# Versa64Cart_v1_3.net
KiCad netlist of a schematic drawn in EAGLE
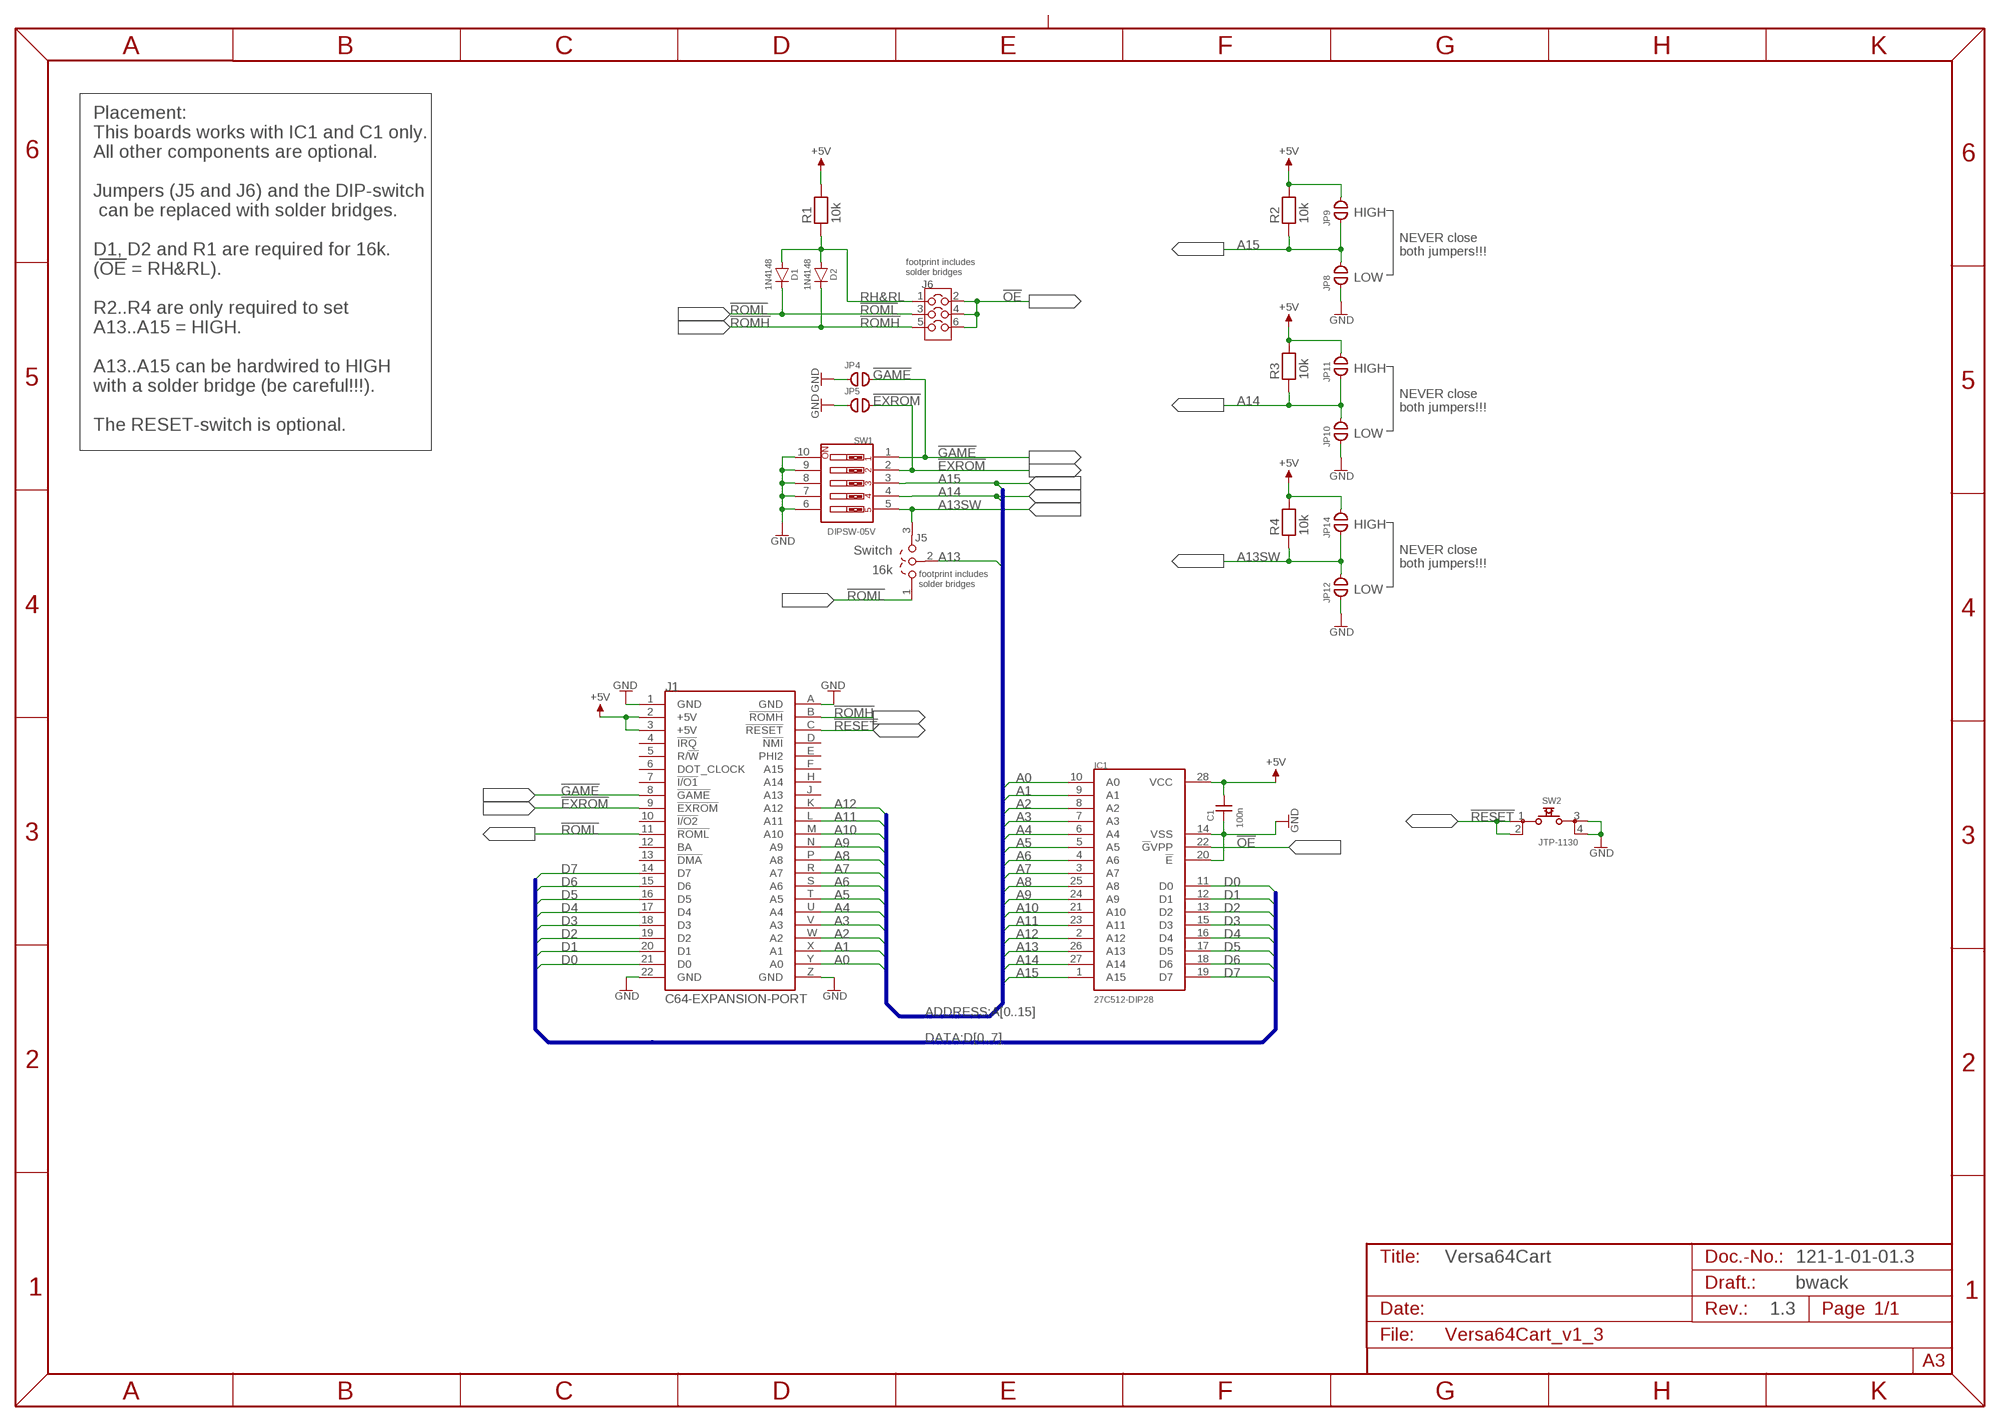
[diagram p0: schematic, sheet 1]

(export (version "E")
  (design (tool "Eeschema 10.0.6"))
  (components
    (comp (ref "C1")
      (value "100n")
      (footprint "eagle-import:C-2,5")
      (libsource (lib "eagle-import") (part "CAP01"))
    )
    (comp (ref "D1")
      (value "1N4148")
      (footprint "eagle-import:DO-35")
      (libsource (lib "eagle-import") (part "1N4148"))
    )
    (comp (ref "D2")
      (value "1N4148")
      (footprint "eagle-import:DO-35")
      (libsource (lib "eagle-import") (part "1N4148"))
    )
    (comp (ref "IC1")
      (value "27C512-DIP28")
      (footprint "eagle-import:DIL28-6")
      (libsource (lib "eagle-import") (part "M27C512-DIP28"))
    )
    (comp (ref "J1")
      (value "C64-EXPANSION-PORT")
      (footprint "eagle-import:EXPPORT")
      (libsource (lib "eagle-import") (part "C64-EXPANSIONP"))
    )
    (comp (ref "J5")
      (value "COMBI-3P")
      (footprint "eagle-import:COMBI-3P")
      (libsource (lib "eagle-import") (part "COMBI-3P"))
    )
    (comp (ref "J6")
      (value "COMBI-3X2P")
      (footprint "eagle-import:COMBI-3X2")
      (fields (field (name "SPICEPREFIX") "X"))
      (libsource (lib "eagle-import") (part "COMBI-3X2P"))
    )
    (comp (ref "JP4")
      (value "OPEN")
      (footprint "eagle-import:CP_OP")
      (libsource (lib "eagle-import") (part "OPEN"))
    )
    (comp (ref "JP5")
      (value "OPEN")
      (footprint "eagle-import:CP_OP")
      (libsource (lib "eagle-import") (part "OPEN"))
    )
    (comp (ref "JP8")
      (value "OPEN")
      (footprint "eagle-import:CP_OP")
      (libsource (lib "eagle-import") (part "OPEN"))
    )
    (comp (ref "JP9")
      (value "OPEN")
      (footprint "eagle-import:CP_OP")
      (libsource (lib "eagle-import") (part "OPEN"))
    )
    (comp (ref "JP10")
      (value "OPEN")
      (footprint "eagle-import:CP_OP")
      (libsource (lib "eagle-import") (part "OPEN"))
    )
    (comp (ref "JP11")
      (value "OPEN")
      (footprint "eagle-import:CP_OP")
      (libsource (lib "eagle-import") (part "OPEN"))
    )
    (comp (ref "JP12")
      (value "OPEN")
      (footprint "eagle-import:CP_OP")
      (libsource (lib "eagle-import") (part "OPEN"))
    )
    (comp (ref "JP14")
      (value "OPEN")
      (footprint "eagle-import:CP_OP")
      (libsource (lib "eagle-import") (part "OPEN"))
    )
    (comp (ref "R1")
      (value "10k")
      (footprint "eagle-import:R-10")
      (libsource (lib "eagle-import") (part "RES04"))
    )
    (comp (ref "R2")
      (value "10k")
      (footprint "eagle-import:R-10")
      (libsource (lib "eagle-import") (part "RES04"))
    )
    (comp (ref "R3")
      (value "10k")
      (footprint "eagle-import:R-10")
      (libsource (lib "eagle-import") (part "RES04"))
    )
    (comp (ref "R4")
      (value "10k")
      (footprint "eagle-import:R-10")
      (libsource (lib "eagle-import") (part "RES04"))
    )
    (comp (ref "SW1")
      (value "DIPSW-05V")
      (footprint "eagle-import:DIPSW-05V")
      (libsource (lib "eagle-import") (part "DIPSW-05V"))
    )
    (comp (ref "SW2")
      (value "JTP-1130")
      (footprint "eagle-import:JTP-1130")
      (libsource (lib "eagle-import") (part "JTP-1130"))
    )
  )
  (nets
    (net (code "25") (name "+5V") (class "Default")
      (node (ref "C1") (pin "2") (pinfunction "2_2") (pintype "passive"))
      (node (ref "IC1") (pin "28") (pinfunction "VCC_28") (pintype "power_in"))
      (node (ref "J1") (pin "2") (pinfunction "+5V_2") (pintype "power_in"))
      (node (ref "J1") (pin "3") (pinfunction "+5V_3") (pintype "power_in"))
      (node (ref "JP11") (pin "2") (pinfunction "2_2") (pintype "passive"))
      (node (ref "JP14") (pin "2") (pinfunction "2_2") (pintype "passive"))
      (node (ref "JP9") (pin "2") (pinfunction "2_2") (pintype "passive"))
      (node (ref "R1") (pin "2") (pinfunction "2_2") (pintype "passive"))
      (node (ref "R2") (pin "2") (pinfunction "2_2") (pintype "passive"))
      (node (ref "R3") (pin "2") (pinfunction "2_2") (pintype "passive"))
      (node (ref "R4") (pin "2") (pinfunction "2_2") (pintype "passive"))
    )
    (net (code "26") (name "/A0") (class "Default")
      (node (ref "IC1") (pin "10") (pinfunction "A0_10") (pintype "input"))
      (node (ref "J1") (pin "Y") (pinfunction "A0_Y") (pintype "bidirectional"))
    )
    (net (code "27") (name "/A1") (class "Default")
      (node (ref "IC1") (pin "9") (pinfunction "A1_9") (pintype "input"))
      (node (ref "J1") (pin "X") (pinfunction "A1_X") (pintype "bidirectional"))
    )
    (net (code "28") (name "/A2") (class "Default")
      (node (ref "IC1") (pin "8") (pinfunction "A2_8") (pintype "input"))
      (node (ref "J1") (pin "W") (pinfunction "A2_W") (pintype "bidirectional"))
    )
    (net (code "29") (name "/A3") (class "Default")
      (node (ref "IC1") (pin "7") (pinfunction "A3_7") (pintype "input"))
      (node (ref "J1") (pin "V") (pinfunction "A3_V") (pintype "bidirectional"))
    )
    (net (code "30") (name "/A4") (class "Default")
      (node (ref "IC1") (pin "6") (pinfunction "A4_6") (pintype "input"))
      (node (ref "J1") (pin "U") (pinfunction "A4_U") (pintype "bidirectional"))
    )
    (net (code "31") (name "/A5") (class "Default")
      (node (ref "IC1") (pin "5") (pinfunction "A5_5") (pintype "input"))
      (node (ref "J1") (pin "T") (pinfunction "A5_T") (pintype "bidirectional"))
    )
    (net (code "32") (name "/A6") (class "Default")
      (node (ref "IC1") (pin "4") (pinfunction "A6_4") (pintype "input"))
      (node (ref "J1") (pin "S") (pinfunction "A6_S") (pintype "bidirectional"))
    )
    (net (code "33") (name "/A7") (class "Default")
      (node (ref "IC1") (pin "3") (pinfunction "A7_3") (pintype "input"))
      (node (ref "J1") (pin "R") (pinfunction "A7_R") (pintype "bidirectional"))
    )
    (net (code "34") (name "/A8") (class "Default")
      (node (ref "IC1") (pin "25") (pinfunction "A8_25") (pintype "input"))
      (node (ref "J1") (pin "P") (pinfunction "A8_P") (pintype "bidirectional"))
    )
    (net (code "35") (name "/A9") (class "Default")
      (node (ref "IC1") (pin "24") (pinfunction "A9_24") (pintype "input"))
      (node (ref "J1") (pin "N") (pinfunction "A9_N") (pintype "bidirectional"))
    )
    (net (code "36") (name "/A10") (class "Default")
      (node (ref "IC1") (pin "21") (pinfunction "A10_21") (pintype "input"))
      (node (ref "J1") (pin "M") (pinfunction "A10_M") (pintype "bidirectional"))
    )
    (net (code "37") (name "/A11") (class "Default")
      (node (ref "IC1") (pin "23") (pinfunction "A11_23") (pintype "input"))
      (node (ref "J1") (pin "L") (pinfunction "A11_L") (pintype "bidirectional"))
    )
    (net (code "38") (name "/A12") (class "Default")
      (node (ref "IC1") (pin "2") (pinfunction "A12_2") (pintype "input"))
      (node (ref "J1") (pin "K") (pinfunction "A12_K") (pintype "bidirectional"))
    )
    (net (code "39") (name "/A13") (class "Default")
      (node (ref "IC1") (pin "26") (pinfunction "A13_26") (pintype "input"))
      (node (ref "J5") (pin "2") (pinfunction "2_2") (pintype "bidirectional"))
    )
    (net (code "40") (name "/A13SW") (class "Default")
      (node (ref "J5") (pin "3") (pinfunction "3_3") (pintype "bidirectional"))
      (node (ref "JP12") (pin "2") (pinfunction "2_2") (pintype "passive"))
      (node (ref "JP14") (pin "1") (pinfunction "1_1") (pintype "passive"))
      (node (ref "R4") (pin "1") (pinfunction "1_1") (pintype "passive"))
      (node (ref "SW1") (pin "5") (pinfunction "5_5") (pintype "passive"))
    )
    (net (code "41") (name "/A14") (class "Default")
      (node (ref "IC1") (pin "27") (pinfunction "A14_27") (pintype "input"))
      (node (ref "JP10") (pin "2") (pinfunction "2_2") (pintype "passive"))
      (node (ref "JP11") (pin "1") (pinfunction "1_1") (pintype "passive"))
      (node (ref "R3") (pin "1") (pinfunction "1_1") (pintype "passive"))
      (node (ref "SW1") (pin "4") (pinfunction "4_4") (pintype "passive"))
    )
    (net (code "42") (name "/A15") (class "Default")
      (node (ref "IC1") (pin "1") (pinfunction "A15_1") (pintype "input"))
      (node (ref "JP8") (pin "2") (pinfunction "2_2") (pintype "passive"))
      (node (ref "JP9") (pin "1") (pinfunction "1_1") (pintype "passive"))
      (node (ref "R2") (pin "1") (pinfunction "1_1") (pintype "passive"))
      (node (ref "SW1") (pin "3") (pinfunction "3_3") (pintype "passive"))
    )
    (net (code "44") (name "/D0") (class "Default")
      (node (ref "IC1") (pin "11") (pinfunction "D0_11") (pintype "bidirectional"))
      (node (ref "J1") (pin "21") (pinfunction "D0_21") (pintype "bidirectional"))
    )
    (net (code "45") (name "/D1") (class "Default")
      (node (ref "IC1") (pin "12") (pinfunction "D1_12") (pintype "bidirectional"))
      (node (ref "J1") (pin "20") (pinfunction "D1_20") (pintype "bidirectional"))
    )
    (net (code "46") (name "/D2") (class "Default")
      (node (ref "IC1") (pin "13") (pinfunction "D2_13") (pintype "bidirectional"))
      (node (ref "J1") (pin "19") (pinfunction "D2_19") (pintype "bidirectional"))
    )
    (net (code "47") (name "/D3") (class "Default")
      (node (ref "IC1") (pin "15") (pinfunction "D3_15") (pintype "bidirectional"))
      (node (ref "J1") (pin "18") (pinfunction "D3_18") (pintype "bidirectional"))
    )
    (net (code "48") (name "/D4") (class "Default")
      (node (ref "IC1") (pin "16") (pinfunction "D4_16") (pintype "bidirectional"))
      (node (ref "J1") (pin "17") (pinfunction "D4_17") (pintype "bidirectional"))
    )
    (net (code "49") (name "/D5") (class "Default")
      (node (ref "IC1") (pin "17") (pinfunction "D5_17") (pintype "bidirectional"))
      (node (ref "J1") (pin "16") (pinfunction "D5_16") (pintype "bidirectional"))
    )
    (net (code "50") (name "/D6") (class "Default")
      (node (ref "IC1") (pin "18") (pinfunction "D6_18") (pintype "bidirectional"))
      (node (ref "J1") (pin "15") (pinfunction "D6_15") (pintype "bidirectional"))
    )
    (net (code "51") (name "/D7") (class "Default")
      (node (ref "IC1") (pin "19") (pinfunction "D7_19") (pintype "bidirectional"))
      (node (ref "J1") (pin "14") (pinfunction "D7_14") (pintype "bidirectional"))
    )
    (net (code "53") (name "/RH&RL") (class "Default")
      (node (ref "D1") (pin "A") (pinfunction "A_A") (pintype "passive"))
      (node (ref "D2") (pin "A") (pinfunction "A_A") (pintype "passive"))
      (node (ref "J6") (pin "1") (pinfunction "1_1") (pintype "bidirectional"))
      (node (ref "R1") (pin "1") (pinfunction "1_1") (pintype "passive"))
    )
    (net (code "54") (name "/~{EXROM}") (class "Default")
      (node (ref "J1") (pin "9") (pinfunction "~{EXROM}_9") (pintype "input"))
      (node (ref "JP5") (pin "2") (pinfunction "2_2") (pintype "passive"))
      (node (ref "SW1") (pin "2") (pinfunction "2_2") (pintype "passive"))
    )
    (net (code "55") (name "/~{GAME}") (class "Default")
      (node (ref "J1") (pin "8") (pinfunction "~{GAME}_8") (pintype "input"))
      (node (ref "JP4") (pin "2") (pinfunction "2_2") (pintype "passive"))
      (node (ref "SW1") (pin "1") (pinfunction "1_1") (pintype "passive"))
    )
    (net (code "56") (name "/~{OE}") (class "Default")
      (node (ref "IC1") (pin "22") (pinfunction "~{G}VPP_22") (pintype "input"))
      (node (ref "J6") (pin "2") (pinfunction "2_2") (pintype "bidirectional"))
      (node (ref "J6") (pin "4") (pinfunction "4_4") (pintype "bidirectional"))
      (node (ref "J6") (pin "6") (pinfunction "6_6") (pintype "bidirectional"))
    )
    (net (code "57") (name "/~{RESET}") (class "Default")
      (node (ref "J1") (pin "C") (pinfunction "~{RESET}_C") (pintype "open_collector"))
      (node (ref "SW2") (pin "1") (pinfunction "1_1") (pintype "passive"))
      (node (ref "SW2") (pin "2") (pinfunction "2_2") (pintype "passive"))
    )
    (net (code "58") (name "/~{ROMH}") (class "Default")
      (node (ref "D2") (pin "K") (pinfunction "K_K") (pintype "passive"))
      (node (ref "J1") (pin "B") (pinfunction "~{ROMH}_B") (pintype "output"))
      (node (ref "J6") (pin "5") (pinfunction "5_5") (pintype "bidirectional"))
    )
    (net (code "59") (name "/~{ROML}") (class "Default")
      (node (ref "D1") (pin "K") (pinfunction "K_K") (pintype "passive"))
      (node (ref "J1") (pin "11") (pinfunction "~{ROML}_11") (pintype "output"))
      (node (ref "J5") (pin "1") (pinfunction "1_1") (pintype "bidirectional"))
      (node (ref "J6") (pin "3") (pinfunction "3_3") (pintype "bidirectional"))
    )
    (net (code "60") (name "GND") (class "Default")
      (node (ref "C1") (pin "1") (pinfunction "1_1") (pintype "passive"))
      (node (ref "IC1") (pin "14") (pinfunction "VSS_14") (pintype "power_in"))
      (node (ref "IC1") (pin "20") (pinfunction "~{E}_20") (pintype "input"))
      (node (ref "J1") (pin "1") (pinfunction "GND_1") (pintype "power_in"))
      (node (ref "J1") (pin "22") (pinfunction "GND_22") (pintype "power_in"))
      (node (ref "J1") (pin "A") (pinfunction "GND_A") (pintype "power_in"))
      (node (ref "J1") (pin "Z") (pinfunction "GND_Z") (pintype "power_in"))
      (node (ref "JP10") (pin "1") (pinfunction "1_1") (pintype "passive"))
      (node (ref "JP12") (pin "1") (pinfunction "1_1") (pintype "passive"))
      (node (ref "JP4") (pin "1") (pinfunction "1_1") (pintype "passive"))
      (node (ref "JP5") (pin "1") (pinfunction "1_1") (pintype "passive"))
      (node (ref "JP8") (pin "1") (pinfunction "1_1") (pintype "passive"))
      (node (ref "SW1") (pin "10") (pinfunction "10_10") (pintype "passive"))
      (node (ref "SW1") (pin "6") (pinfunction "6_6") (pintype "passive"))
      (node (ref "SW1") (pin "7") (pinfunction "7_7") (pintype "passive"))
      (node (ref "SW1") (pin "8") (pinfunction "8_8") (pintype "passive"))
      (node (ref "SW1") (pin "9") (pinfunction "9_9") (pintype "passive"))
      (node (ref "SW2") (pin "3") (pinfunction "3_3") (pintype "passive"))
      (node (ref "SW2") (pin "4") (pinfunction "4_4") (pintype "passive"))
    )
    (net (code "61") (name "unconnected-(J1-A13-PadJ)") (class "Default")
      (node (ref "J1") (pin "J") (pinfunction "A13_J") (pintype "bidirectional"))
    )
    (net (code "62") (name "unconnected-(J1-A14-PadH)") (class "Default")
      (node (ref "J1") (pin "H") (pinfunction "A14_H") (pintype "bidirectional"))
    )
    (net (code "63") (name "unconnected-(J1-A15-PadF)") (class "Default")
      (node (ref "J1") (pin "F") (pinfunction "A15_F") (pintype "bidirectional"))
    )
    (net (code "64") (name "unconnected-(J1-BA-Pad12)") (class "Default")
      (node (ref "J1") (pin "12") (pinfunction "BA_12") (pintype "output"))
    )
    (net (code "65") (name "unconnected-(J1-DOT_CLOCK-Pad6)") (class "Default")
      (node (ref "J1") (pin "6") (pinfunction "DOT_CLOCK_6") (pintype "output"))
    )
    (net (code "66") (name "unconnected-(J1-PHI2-PadE)") (class "Default")
      (node (ref "J1") (pin "E") (pinfunction "PHI2_E") (pintype "output"))
    )
    (net (code "67") (name "unconnected-(J1-R{slash}~{W}-Pad5)") (class "Default")
      (node (ref "J1") (pin "5") (pinfunction "R/~{W}_5") (pintype "output"))
    )
    (net (code "68") (name "unconnected-(J1-~{DMA}-Pad13)") (class "Default")
      (node (ref "J1") (pin "13") (pinfunction "~{DMA}_13") (pintype "input"))
    )
    (net (code "69") (name "unconnected-(J1-~{IRQ}-Pad4)") (class "Default")
      (node (ref "J1") (pin "4") (pinfunction "~{IRQ}_4") (pintype "input"))
    )
    (net (code "70") (name "unconnected-(J1-~{I{slash}O1}-Pad7)") (class "Default")
      (node (ref "J1") (pin "7") (pinfunction "~{I/O1}_7") (pintype "output"))
    )
    (net (code "71") (name "unconnected-(J1-~{I{slash}O2}-Pad10)") (class "Default")
      (node (ref "J1") (pin "10") (pinfunction "~{I/O2}_10") (pintype "output"))
    )
    (net (code "72") (name "unconnected-(J1-~{NMI}-PadD)") (class "Default")
      (node (ref "J1") (pin "D") (pinfunction "~{NMI}_D") (pintype "input"))
    )
  )
)
